# Power_Supply.net
KiCad netlist of a schematic drawn in Altium Designer
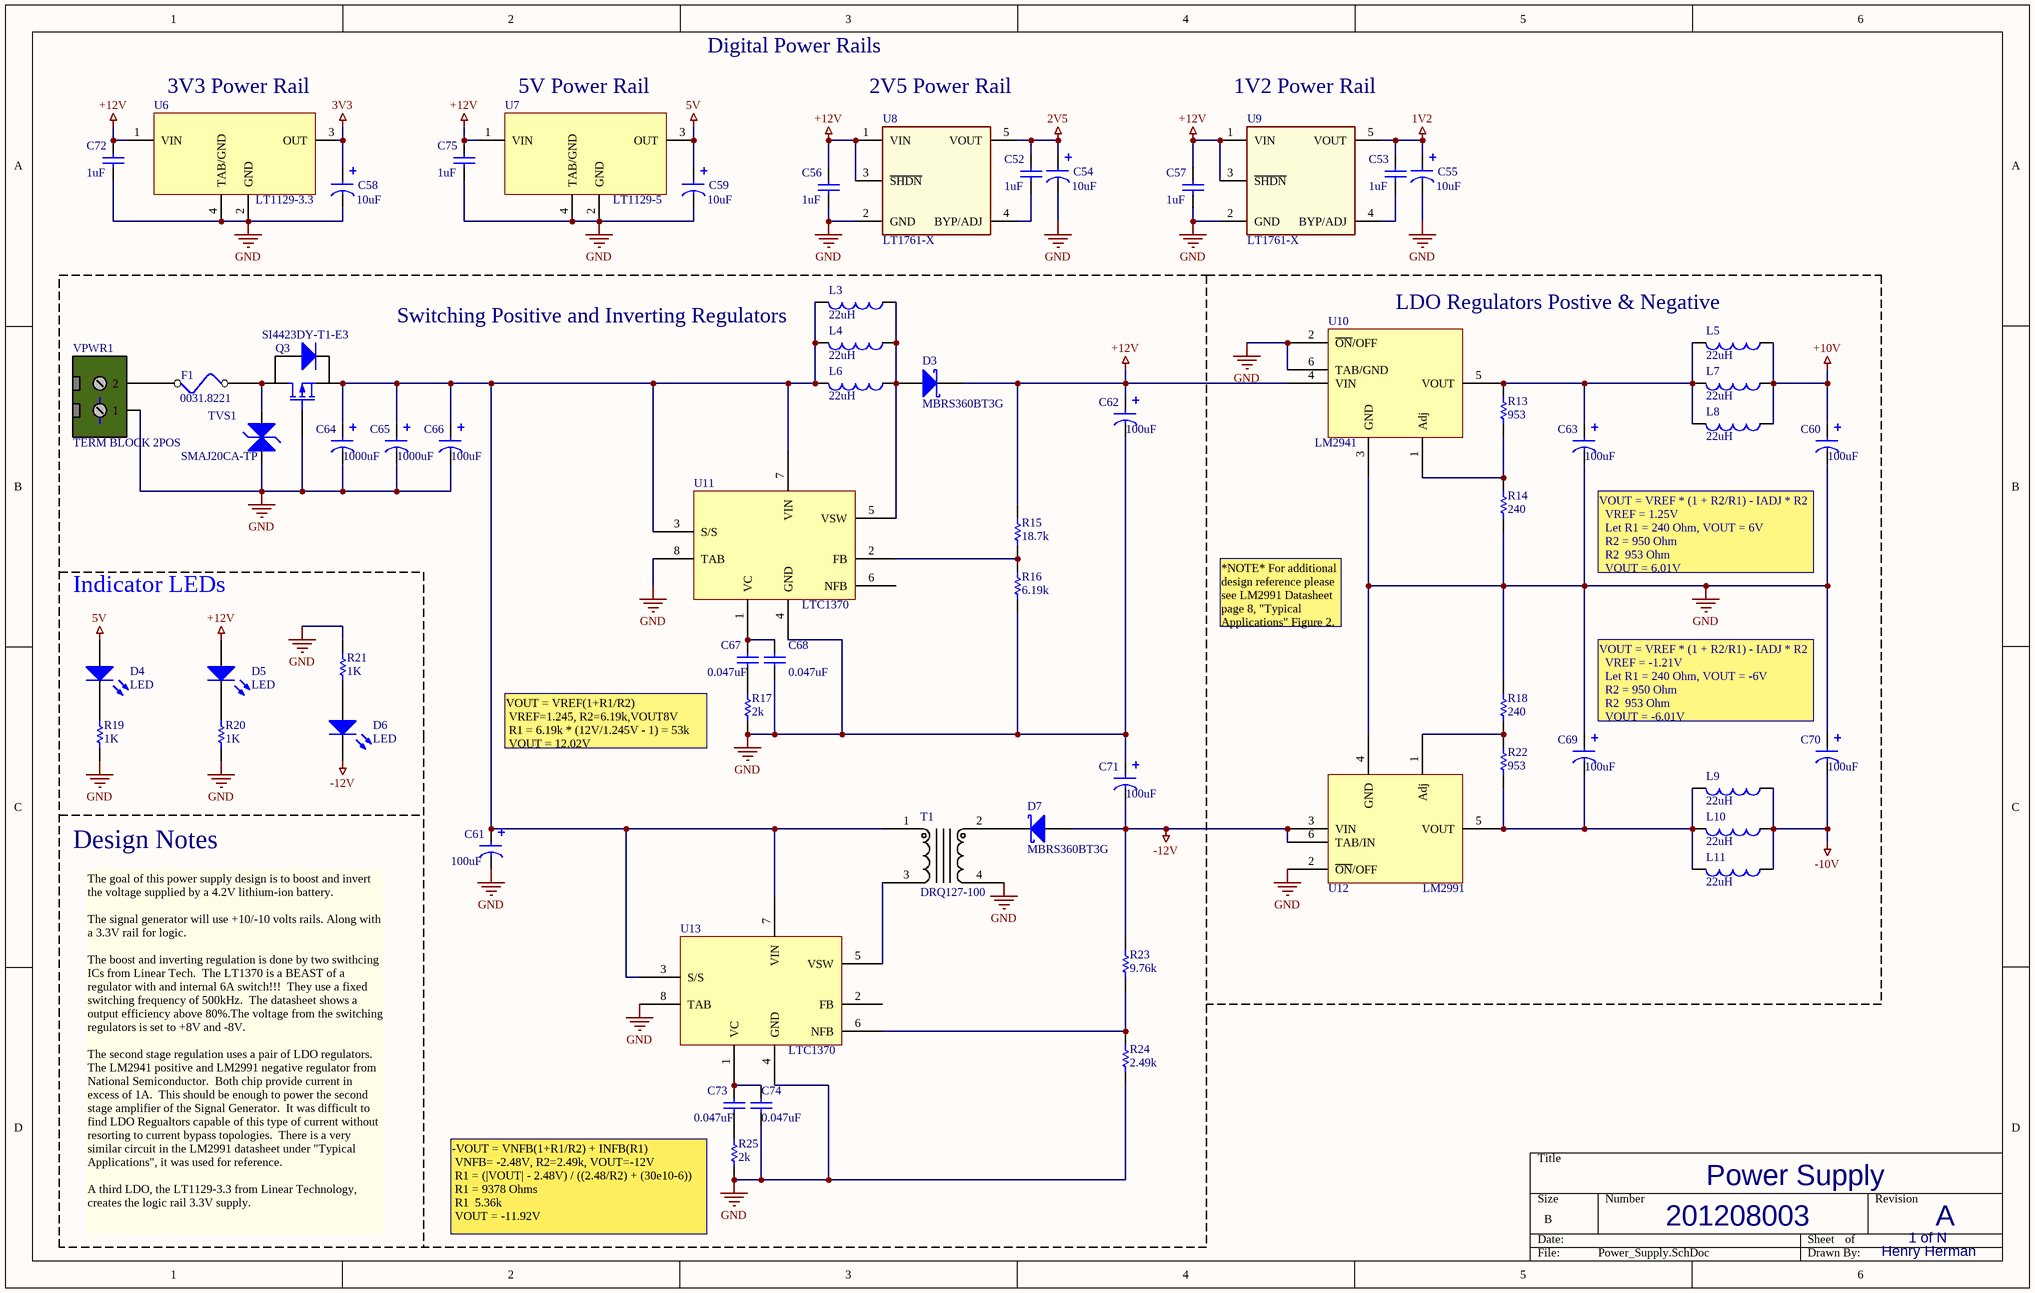
[diagram p0: Power_Supply.SchDoc]

(export (version "E")
  (design (tool "Eeschema 10.0.6"))
  (components
    (comp (ref "C52")
      (value "CAP")
      (footprint "SM/C_0603")
      (fields (field (name "LABEL") "1uF"))
      (libsource (lib "Henry1_20_2010") (part "CAP"))
    )
    (comp (ref "C53")
      (value "CAP")
      (footprint "SM/C_0603")
      (fields (field (name "LABEL") "1uF"))
      (libsource (lib "Henry1_20_2010") (part "CAP"))
    )
    (comp (ref "C54")
      (value "CAP_POL")
      (footprint "SM/C_POL_0805")
      (description "CAP")
      (fields (field (name "LABEL") "10uF"))
      (libsource (lib "Henry1_20_2010") (part "CAP_POL"))
    )
    (comp (ref "C55")
      (value "CAP_POL")
      (footprint "SM/C_POL_0805")
      (description "CAP")
      (fields (field (name "LABEL") "10uF"))
      (libsource (lib "Henry1_20_2010") (part "CAP_POL"))
    )
    (comp (ref "C56")
      (value "CAP")
      (footprint "SM/C_0603")
      (fields (field (name "LABEL") "1uF"))
      (libsource (lib "Henry1_20_2010") (part "CAP"))
    )
    (comp (ref "C57")
      (value "CAP")
      (footprint "SM/C_0603")
      (fields (field (name "LABEL") "1uF"))
      (libsource (lib "Henry1_20_2010") (part "CAP"))
    )
    (comp (ref "C58")
      (value "10uF")
      (footprint "SM/C_POL_0805")
      (description "CAP")
      (fields (field (name "Comment") "CAP_POL"))
      (libsource (lib "Henry1_20_2010") (part "CAP_POL"))
    )
    (comp (ref "C59")
      (value "CAP_POL")
      (footprint "SM/C_POL_0805")
      (description "CAP")
      (fields (field (name "ALTIUM_VALUE") "10uF"))
      (libsource (lib "Henry1_20_2010") (part "CAP_POL"))
    )
    (comp (ref "C60")
      (value "CAP_POL")
      (footprint "SM/CT_6032_12")
      (description "CAP")
      (fields (field (name "LABEL") "100uF"))
      (libsource (lib "Henry1_20_2010") (part "CAP_POL"))
    )
    (comp (ref "C61")
      (value "CAP_POL")
      (footprint "SM/CT_6032_12")
      (description "CAP")
      (fields (field (name "LABEL") "100uF"))
      (libsource (lib "Henry1_20_2010") (part "CAP_POL"))
    )
    (comp (ref "C62")
      (value "CAP_POL")
      (footprint "SM/CT_6032_12")
      (description "CAP")
      (fields (field (name "LABEL") "100uF"))
      (libsource (lib "Henry1_20_2010") (part "CAP_POL"))
    )
    (comp (ref "C63")
      (value "CAP_POL")
      (footprint "SM/CT_6032_12")
      (description "CAP")
      (fields (field (name "LABEL") "100uF"))
      (libsource (lib "Henry1_20_2010") (part "CAP_POL"))
    )
    (comp (ref "C64")
      (value "CAP_POL")
      (footprint "CAP-CAN-SMD-POL-12.5mmDia")
      (description "CAP")
      (fields (field (name "LABEL") "1000uF"))
      (libsource (lib "Henry1_20_2010") (part "CAP_POL"))
    )
    (comp (ref "C65")
      (value "CAP_POL")
      (footprint "CAP-CAN-SMD-POL-12.5mmDia")
      (description "CAP")
      (fields (field (name "LABEL") "1000uF"))
      (libsource (lib "Henry1_20_2010") (part "CAP_POL"))
    )
    (comp (ref "C66")
      (value "CAP_POL")
      (footprint "SM/CT_6032_12")
      (description "CAP")
      (fields (field (name "LABEL") "100uF"))
      (libsource (lib "Henry1_20_2010") (part "CAP_POL"))
    )
    (comp (ref "C67")
      (value "CAP")
      (footprint "SM/C_0603")
      (fields (field (name "LABEL") "0.047uF"))
      (libsource (lib "Henry1_20_2010") (part "CAP"))
    )
    (comp (ref "C68")
      (value "CAP")
      (footprint "SM/C_0603")
      (fields (field (name "LABEL") "0.047uF"))
      (libsource (lib "Henry1_20_2010") (part "CAP"))
    )
    (comp (ref "C69")
      (value "CAP_POL")
      (footprint "SM/CT_6032_12")
      (description "CAP")
      (fields (field (name "LABEL") "100uF"))
      (libsource (lib "Henry1_20_2010") (part "CAP_POL"))
    )
    (comp (ref "C70")
      (value "CAP_POL")
      (footprint "SM/CT_6032_12")
      (description "CAP")
      (fields (field (name "LABEL") "100uF"))
      (libsource (lib "Henry1_20_2010") (part "CAP_POL"))
    )
    (comp (ref "C71")
      (value "CAP_POL")
      (footprint "SM/CT_6032_12")
      (description "CAP")
      (fields (field (name "LABEL") "100uF"))
      (libsource (lib "Henry1_20_2010") (part "CAP_POL"))
    )
    (comp (ref "C72")
      (value "CAP")
      (footprint "SM/C_0603")
      (fields (field (name "LABEL") "1uF"))
      (libsource (lib "Henry1_20_2010") (part "CAP"))
    )
    (comp (ref "C73")
      (value "CAP")
      (footprint "SM/C_0603")
      (fields (field (name "LABEL") "0.047uF"))
      (libsource (lib "Henry1_20_2010") (part "CAP"))
    )
    (comp (ref "C74")
      (value "CAP")
      (footprint "SM/C_0603")
      (fields (field (name "LABEL") "0.047uF"))
      (libsource (lib "Henry1_20_2010") (part "CAP"))
    )
    (comp (ref "C75")
      (value "CAP")
      (footprint "SM/C_0603")
      (fields (field (name "LABEL") "1uF"))
      (libsource (lib "Henry1_20_2010") (part "CAP"))
    )
    (comp (ref "D3")
      (value "MBRS360BT3G")
      (footprint "DPAK-MBRD835L")
      (libsource (lib "Henry1_20_2010") (part "Schottky Diode"))
    )
    (comp (ref "D4") (value "LED") (footprint "LED-1206") (libsource (lib "Henry1_20_2010") (part "LED")))
    (comp (ref "D5") (value "LED") (footprint "LED-1206") (libsource (lib "Henry1_20_2010") (part "LED")))
    (comp (ref "D6") (value "LED") (footprint "LED-1206") (libsource (lib "Henry1_20_2010") (part "LED")))
    (comp (ref "D7")
      (value "MBRS360BT3G")
      (footprint "DPAK-MBRD835L")
      (libsource (lib "Henry1_20_2010") (part "Schottky Diode"))
    )
    (comp (ref "F1")
      (value "0031.8221")
      (footprint "SCHURTER/SMD/2 PADS/0031.8221")
      (description "FUSEHOLDER BLACK FOR SMD 5X20MM")
      (libsource (lib "FriedParts") (part "FUSE"))
    )
    (comp (ref "L3")
      (value "22uH")
      (footprint "G_JMETRIC/TDK/SLE10145")
      (description "INDUCTOR SHIELD PWR 22UH 10145")
      (fields (field (name "MFRPARTNUM") "SLF10145T-220M1R9-PF"))
      (libsource (lib "FriedParts") (part "INDUCTOR"))
    )
    (comp (ref "L4")
      (value "22uH")
      (footprint "G_JMETRIC/TDK/SLE10145")
      (description "INDUCTOR SHIELD PWR 22UH 10145")
      (fields (field (name "MFRPARTNUM") "SLF10145T-220M1R9-PF"))
      (libsource (lib "FriedParts") (part "INDUCTOR"))
    )
    (comp (ref "L5")
      (value "22uH")
      (footprint "G_JMETRIC/TDK/SLE10145")
      (description "INDUCTOR SHIELD PWR 22UH 10145")
      (fields (field (name "MFRPARTNUM") "SLF10145T-220M1R9-PF"))
      (libsource (lib "FriedParts") (part "INDUCTOR"))
    )
    (comp (ref "L6")
      (value "22uH")
      (footprint "G_JMETRIC/TDK/SLE10145")
      (description "INDUCTOR SHIELD PWR 22UH 10145")
      (fields (field (name "MFRPARTNUM") "SLF10145T-220M1R9-PF"))
      (libsource (lib "FriedParts") (part "INDUCTOR"))
    )
    (comp (ref "L7")
      (value "22uH")
      (footprint "G_JMETRIC/TDK/SLE10145")
      (description "INDUCTOR SHIELD PWR 22UH 10145")
      (fields (field (name "MFRPARTNUM") "SLF10145T-220M1R9-PF"))
      (libsource (lib "FriedParts") (part "INDUCTOR"))
    )
    (comp (ref "L8")
      (value "22uH")
      (footprint "G_JMETRIC/TDK/SLE10145")
      (description "INDUCTOR SHIELD PWR 22UH 10145")
      (fields (field (name "MFRPARTNUM") "SLF10145T-220M1R9-PF"))
      (libsource (lib "FriedParts") (part "INDUCTOR"))
    )
    (comp (ref "L9")
      (value "22uH")
      (footprint "G_JMETRIC/TDK/SLE10145")
      (description "INDUCTOR SHIELD PWR 22UH 10145")
      (fields (field (name "MFRPARTNUM") "SLF10145T-220M1R9-PF"))
      (libsource (lib "FriedParts") (part "INDUCTOR"))
    )
    (comp (ref "L10")
      (value "22uH")
      (footprint "G_JMETRIC/TDK/SLE10145")
      (description "INDUCTOR SHIELD PWR 22UH 10145")
      (fields (field (name "MFRPARTNUM") "SLF10145T-220M1R9-PF"))
      (libsource (lib "FriedParts") (part "INDUCTOR"))
    )
    (comp (ref "L11")
      (value "22uH")
      (footprint "G_JMETRIC/TDK/SLE10145")
      (description "INDUCTOR SHIELD PWR 22UH 10145")
      (fields (field (name "MFRPARTNUM") "SLF10145T-220M1R9-PF"))
      (libsource (lib "FriedParts") (part "INDUCTOR"))
    )
    (comp (ref "Q3")
      (value "SI4423DY-T1-E3")
      (footprint "SOIC-8-Lead-Vishay-PFET")
      (description "mosfet,p ch,20v,10a,8soic; transistor polarity:p channel;")
      (libsource (lib "FriedParts") (part "P-Channel 20V D-S MOSFET"))
    )
    (comp (ref "R13")
      (value "953")
      (footprint "SM/R_0603")
      (description "Resistor")
      (fields (field (name "Comment") "Res") (field (name "PUBLISHER") "Altium Limited"))
      (libsource (lib "Henry1_20_2010") (part "Res"))
    )
    (comp (ref "R14")
      (value "240")
      (footprint "SM/R_0603")
      (description "Resistor")
      (fields (field (name "Comment") "Res") (field (name "PUBLISHER") "Altium Limited"))
      (libsource (lib "Henry1_20_2010") (part "Res"))
    )
    (comp (ref "R15")
      (value "18.7k")
      (footprint "SM/R_0603")
      (description "Resistor")
      (fields (field (name "Comment") "Res") (field (name "PUBLISHER") "Altium Limited"))
      (libsource (lib "Henry1_20_2010") (part "Res"))
    )
    (comp (ref "R16")
      (value "6.19k")
      (footprint "SM/R_0603")
      (description "Resistor")
      (fields (field (name "Comment") "Res") (field (name "PUBLISHER") "Altium Limited"))
      (libsource (lib "Henry1_20_2010") (part "Res"))
    )
    (comp (ref "R17")
      (value "2k")
      (footprint "SM/R_0603")
      (description "Resistor")
      (fields (field (name "Comment") "Res") (field (name "PUBLISHER") "Altium Limited"))
      (libsource (lib "Henry1_20_2010") (part "Res"))
    )
    (comp (ref "R18")
      (value "240")
      (footprint "SM/R_0603")
      (description "Resistor")
      (fields (field (name "Comment") "Res") (field (name "PUBLISHER") "Altium Limited"))
      (libsource (lib "Henry1_20_2010") (part "Res"))
    )
    (comp (ref "R19")
      (value "1K")
      (footprint "SM/R_0603")
      (description "Resistor")
      (fields (field (name "Comment") "Res") (field (name "PUBLISHER") "Altium Limited"))
      (libsource (lib "Henry1_20_2010") (part "Res"))
    )
    (comp (ref "R20")
      (value "1K")
      (footprint "SM/R_0603")
      (description "Resistor")
      (fields (field (name "Comment") "Res") (field (name "PUBLISHER") "Altium Limited"))
      (libsource (lib "Henry1_20_2010") (part "Res"))
    )
    (comp (ref "R21")
      (value "1K")
      (footprint "SM/R_0603")
      (description "Resistor")
      (fields (field (name "Comment") "Res") (field (name "PUBLISHER") "Altium Limited"))
      (libsource (lib "Henry1_20_2010") (part "Res"))
    )
    (comp (ref "R22")
      (value "953")
      (footprint "SM/R_0603")
      (description "Resistor")
      (fields (field (name "Comment") "Res") (field (name "PUBLISHER") "Altium Limited"))
      (libsource (lib "Henry1_20_2010") (part "Res"))
    )
    (comp (ref "R23")
      (value "9.76k")
      (footprint "SM/R_0603")
      (description "Resistor")
      (fields (field (name "Comment") "Res") (field (name "PUBLISHER") "Altium Limited"))
      (libsource (lib "Henry1_20_2010") (part "Res"))
    )
    (comp (ref "R24")
      (value "2.49k")
      (footprint "SM/R_0603")
      (description "Resistor")
      (fields (field (name "Comment") "Res") (field (name "PUBLISHER") "Altium Limited"))
      (libsource (lib "Henry1_20_2010") (part "Res"))
    )
    (comp (ref "R25")
      (value "2k")
      (footprint "SM/R_0603")
      (description "Resistor")
      (fields (field (name "Comment") "Res") (field (name "PUBLISHER") "Altium Limited"))
      (libsource (lib "Henry1_20_2010") (part "Res"))
    )
    (comp (ref "T1")
      (value "DRQ127-100")
      (footprint "DRQ127-100")
      (libsource (lib "Henry1_20_2010") (part "DRQ127-100-XFORM-1{colon}1"))
    )
    (comp (ref "TVS1")
      (value "SMAJ20CA-TP")
      (footprint "D0-214AC")
      (description "TVS 400W 12V BIDIRECT SMA")
      (fields (field (name "MFRPARTNUM") "SMAJ12CA-TP"))
      (libsource (lib "FriedParts") (part "SMAJ12CA-TPMC"))
    )
    (comp (ref "U6")
      (value "LT1129-3.3")
      (footprint "SOT223-3Lead-STPackage-LinearTechLT1129-3.3")
      (libsource (lib "Henry1_20_2010") (part "LT1129-3.3"))
    )
    (comp (ref "U7")
      (value "LT1129-5")
      (footprint "SOT223-3Lead-STPackage-LinearTechLT1129-3.3")
      (libsource (lib "Henry1_20_2010") (part "LT1129-5"))
    )
    (comp (ref "U8")
      (value "LT1761-X")
      (footprint "TSOT-23-5Lead-LTC3406A")
      (libsource (lib "Henry1_20_2010") (part "LT1761-X"))
    )
    (comp (ref "U9")
      (value "LT1761-X")
      (footprint "TSOT-23-5Lead-LTC3406A")
      (libsource (lib "Henry1_20_2010") (part "LT1761-X"))
    )
    (comp (ref "U10")
      (value "LM2941")
      (footprint "T0-263- 5Lead - National Semi - LM2941")
      (libsource (lib "Henry1_20_2010") (part "LM2941-LDO Regulator"))
    )
    (comp (ref "U11")
      (value "LTC1370")
      (footprint "DDPak-7Lead-RPackage-linear")
      (libsource (lib "Henry1_20_2010") (part "LT1370"))
    )
    (comp (ref "U12")
      (value "LM2991")
      (footprint "T0-263 5Lead SMP - National Semi - LM2991S")
      (libsource (lib "Henry1_20_2010") (part "LM2991-Negative LDO Regulator"))
    )
    (comp (ref "U13")
      (value "LTC1370")
      (footprint "DDPak-7Lead-RPackage-linear")
      (libsource (lib "Henry1_20_2010") (part "LT1370"))
    )
    (comp (ref "VPWR1")
      (value "TERM BLOCK 2POS")
      (footprint "Conn-ScrewTerminal-2pin-Phoenix")
      (libsource (lib "Henry1_20_2010") (part "2Pin-PhoenixTerminalBlock"))
    )
  )
  (nets
    (net (code "1") (name "+10V") (class "Default")
      (node (ref "C60") (pin "1") (pinfunction "1_1") (pintype "passive"))
      (node (ref "L5") (pin "1") (pinfunction "1_1") (pintype "passive"))
      (node (ref "L7") (pin "1") (pinfunction "1_1") (pintype "passive"))
      (node (ref "L8") (pin "1") (pinfunction "1_1") (pintype "passive"))
    )
    (net (code "2") (name "+12V") (class "Default")
      (node (ref "C56") (pin "2") (pinfunction "2_2") (pintype "passive"))
      (node (ref "C57") (pin "2") (pinfunction "2_2") (pintype "passive"))
      (node (ref "C62") (pin "1") (pinfunction "1_1") (pintype "passive"))
      (node (ref "C72") (pin "2") (pinfunction "2_2") (pintype "passive"))
      (node (ref "C75") (pin "2") (pinfunction "2_2") (pintype "passive"))
      (node (ref "D3") (pin "K") (pinfunction "K_K") (pintype "passive"))
      (node (ref "D5") (pin "1") (pinfunction "A_1") (pintype "passive"))
      (node (ref "R15") (pin "2") (pinfunction "2_2") (pintype "passive"))
      (node (ref "U10") (pin "4") (pinfunction "VIN_4") (pintype "passive"))
      (node (ref "U6") (pin "1") (pinfunction "VIN_1") (pintype "passive"))
      (node (ref "U7") (pin "1") (pinfunction "VIN_1") (pintype "passive"))
      (node (ref "U8") (pin "1") (pinfunction "VIN_1") (pintype "power_in"))
      (node (ref "U8") (pin "3") (pinfunction "~{SHDN}_3") (pintype "power_in"))
      (node (ref "U9") (pin "1") (pinfunction "VIN_1") (pintype "power_in"))
      (node (ref "U9") (pin "3") (pinfunction "~{SHDN}_3") (pintype "power_in"))
    )
    (net (code "3") (name "-10V") (class "Default")
      (node (ref "C70") (pin "2") (pinfunction "2_2") (pintype "passive"))
      (node (ref "L10") (pin "1") (pinfunction "1_1") (pintype "passive"))
      (node (ref "L11") (pin "1") (pinfunction "1_1") (pintype "passive"))
      (node (ref "L9") (pin "1") (pinfunction "1_1") (pintype "passive"))
    )
    (net (code "4") (name "-12V") (class "Default")
      (node (ref "C71") (pin "2") (pinfunction "2_2") (pintype "passive"))
      (node (ref "D6") (pin "2") (pinfunction "K_2") (pintype "passive"))
      (node (ref "D7") (pin "A") (pinfunction "A_A") (pintype "passive"))
      (node (ref "R23") (pin "2") (pinfunction "2_2") (pintype "passive"))
      (node (ref "U12") (pin "3") (pinfunction "VIN_3") (pintype "passive"))
      (node (ref "U12") (pin "6") (pinfunction "TAB/IN_6") (pintype "passive"))
    )
    (net (code "5") (name "1V2") (class "Default")
      (node (ref "C53") (pin "2") (pinfunction "2_2") (pintype "passive"))
      (node (ref "C55") (pin "1") (pinfunction "1_1") (pintype "passive"))
      (node (ref "U9") (pin "5") (pinfunction "VOUT_5") (pintype "power_in"))
    )
    (net (code "6") (name "2V5") (class "Default")
      (node (ref "C52") (pin "2") (pinfunction "2_2") (pintype "passive"))
      (node (ref "C54") (pin "1") (pinfunction "1_1") (pintype "passive"))
      (node (ref "U8") (pin "5") (pinfunction "VOUT_5") (pintype "power_in"))
    )
    (net (code "7") (name "3V3") (class "Default")
      (node (ref "C58") (pin "1") (pinfunction "1_1") (pintype "passive"))
      (node (ref "U6") (pin "3") (pinfunction "OUT_3") (pintype "passive"))
    )
    (net (code "8") (name "5V") (class "Default")
      (node (ref "C59") (pin "1") (pinfunction "1_1") (pintype "passive"))
      (node (ref "D4") (pin "1") (pinfunction "A_1") (pintype "passive"))
      (node (ref "U7") (pin "3") (pinfunction "OUT_3") (pintype "passive"))
    )
    (net (code "9") (name "GND") (class "Default")
      (node (ref "C54") (pin "2") (pinfunction "2_2") (pintype "passive"))
      (node (ref "C55") (pin "2") (pinfunction "2_2") (pintype "passive"))
      (node (ref "C56") (pin "1") (pinfunction "1_1") (pintype "passive"))
      (node (ref "C57") (pin "1") (pinfunction "1_1") (pintype "passive"))
      (node (ref "C58") (pin "2") (pinfunction "2_2") (pintype "passive"))
      (node (ref "C59") (pin "2") (pinfunction "2_2") (pintype "passive"))
      (node (ref "C60") (pin "2") (pinfunction "2_2") (pintype "passive"))
      (node (ref "C61") (pin "2") (pinfunction "2_2") (pintype "passive"))
      (node (ref "C62") (pin "2") (pinfunction "2_2") (pintype "passive"))
      (node (ref "C63") (pin "2") (pinfunction "2_2") (pintype "passive"))
      (node (ref "C64") (pin "2") (pinfunction "2_2") (pintype "passive"))
      (node (ref "C65") (pin "2") (pinfunction "2_2") (pintype "passive"))
      (node (ref "C66") (pin "2") (pinfunction "2_2") (pintype "passive"))
      (node (ref "C68") (pin "1") (pinfunction "1_1") (pintype "passive"))
      (node (ref "C69") (pin "1") (pinfunction "1_1") (pintype "passive"))
      (node (ref "C70") (pin "1") (pinfunction "1_1") (pintype "passive"))
      (node (ref "C71") (pin "1") (pinfunction "1_1") (pintype "passive"))
      (node (ref "C72") (pin "1") (pinfunction "1_1") (pintype "passive"))
      (node (ref "C74") (pin "1") (pinfunction "1_1") (pintype "passive"))
      (node (ref "C75") (pin "1") (pinfunction "1_1") (pintype "passive"))
      (node (ref "Q3") (pin "G") (pinfunction "G_G") (pintype "passive"))
      (node (ref "R14") (pin "1") (pinfunction "1_1") (pintype "passive"))
      (node (ref "R16") (pin "1") (pinfunction "1_1") (pintype "passive"))
      (node (ref "R17") (pin "1") (pinfunction "1_1") (pintype "passive"))
      (node (ref "R18") (pin "2") (pinfunction "2_2") (pintype "passive"))
      (node (ref "R19") (pin "1") (pinfunction "1_1") (pintype "passive"))
      (node (ref "R20") (pin "1") (pinfunction "1_1") (pintype "passive"))
      (node (ref "R21") (pin "2") (pinfunction "2_2") (pintype "passive"))
      (node (ref "R24") (pin "1") (pinfunction "1_1") (pintype "passive"))
      (node (ref "R25") (pin "1") (pinfunction "1_1") (pintype "passive"))
      (node (ref "T1") (pin "4") (pinfunction "4_4") (pintype "passive"))
      (node (ref "TVS1") (pin "C") (pinfunction "1_C") (pintype "passive"))
      (node (ref "U10") (pin "2") (pinfunction "~{ON}/OFF_2") (pintype "passive"))
      (node (ref "U10") (pin "3") (pinfunction "GND_3") (pintype "passive"))
      (node (ref "U10") (pin "6") (pinfunction "TAB/GND_6") (pintype "passive"))
      (node (ref "U11") (pin "4") (pinfunction "GND_4") (pintype "passive"))
      (node (ref "U11") (pin "8") (pinfunction "TAB_8") (pintype "passive"))
      (node (ref "U12") (pin "2") (pinfunction "~{ON}/OFF_2") (pintype "passive"))
      (node (ref "U12") (pin "4") (pinfunction "GND_4") (pintype "passive"))
      (node (ref "U13") (pin "4") (pinfunction "GND_4") (pintype "passive"))
      (node (ref "U13") (pin "8") (pinfunction "TAB_8") (pintype "passive"))
      (node (ref "U6") (pin "2") (pinfunction "GND_2") (pintype "passive"))
      (node (ref "U6") (pin "4") (pinfunction "TAB/GND_4") (pintype "passive"))
      (node (ref "U7") (pin "2") (pinfunction "GND_2") (pintype "passive"))
      (node (ref "U7") (pin "4") (pinfunction "TAB/GND_4") (pintype "passive"))
      (node (ref "U8") (pin "2") (pinfunction "GND_2") (pintype "power_in"))
      (node (ref "U9") (pin "2") (pinfunction "GND_2") (pintype "power_in"))
      (node (ref "VPWR1") (pin "1") (pinfunction "1_1") (pintype "passive"))
    )
    (net (code "10") (name "Net-(C67-Pad1)") (class "Default")
      (node (ref "C67") (pin "1") (pinfunction "1_1") (pintype "passive"))
      (node (ref "R17") (pin "2") (pinfunction "2_2") (pintype "passive"))
    )
    (net (code "11") (name "Net-(C73-Pad1)") (class "Default")
      (node (ref "C73") (pin "1") (pinfunction "1_1") (pintype "passive"))
      (node (ref "R25") (pin "2") (pinfunction "2_2") (pintype "passive"))
    )
    (net (code "12") (name "Net-(D4-K)") (class "Default")
      (node (ref "D4") (pin "2") (pinfunction "K_2") (pintype "passive"))
      (node (ref "R19") (pin "2") (pinfunction "2_2") (pintype "passive"))
    )
    (net (code "13") (name "Net-(D5-K)") (class "Default")
      (node (ref "D5") (pin "2") (pinfunction "K_2") (pintype "passive"))
      (node (ref "R20") (pin "2") (pinfunction "2_2") (pintype "passive"))
    )
    (net (code "14") (name "Net-(D6-A)") (class "Default")
      (node (ref "D6") (pin "1") (pinfunction "A_1") (pintype "passive"))
      (node (ref "R21") (pin "1") (pinfunction "1_1") (pintype "passive"))
    )
    (net (code "15") (name "Net-(D7-PadK)") (class "Default")
      (node (ref "D7") (pin "K") (pinfunction "K_K") (pintype "passive"))
      (node (ref "T1") (pin "2") (pinfunction "2_2") (pintype "passive"))
    )
    (net (code "16") (name "Net-(F1-Pad1)") (class "Default")
      (node (ref "F1") (pin "1") (pinfunction "1_1") (pintype "passive"))
      (node (ref "VPWR1") (pin "2") (pinfunction "2_2") (pintype "passive"))
    )
    (net (code "17") (name "Net-(T1-P1)") (class "Default")
      (node (ref "C61") (pin "1") (pinfunction "1_1") (pintype "passive"))
      (node (ref "C64") (pin "1") (pinfunction "1_1") (pintype "passive"))
      (node (ref "C65") (pin "1") (pinfunction "1_1") (pintype "passive"))
      (node (ref "C66") (pin "1") (pinfunction "1_1") (pintype "passive"))
      (node (ref "L3") (pin "2") (pinfunction "2_2") (pintype "passive"))
      (node (ref "L4") (pin "2") (pinfunction "2_2") (pintype "passive"))
      (node (ref "L6") (pin "2") (pinfunction "2_2") (pintype "passive"))
      (node (ref "Q3") (pin "S") (pinfunction "S_S") (pintype "passive"))
      (node (ref "T1") (pin "1") (pinfunction "P1_1") (pintype "passive"))
      (node (ref "U11") (pin "3") (pinfunction "S/S_3") (pintype "passive"))
      (node (ref "U11") (pin "7") (pinfunction "VIN_7") (pintype "passive"))
      (node (ref "U13") (pin "3") (pinfunction "S/S_3") (pintype "passive"))
      (node (ref "U13") (pin "7") (pinfunction "VIN_7") (pintype "passive"))
    )
    (net (code "18") (name "Net-(TVS1-2)") (class "Default")
      (node (ref "F1") (pin "2") (pinfunction "2_2") (pintype "passive"))
      (node (ref "Q3") (pin "D") (pinfunction "D_D") (pintype "passive"))
      (node (ref "TVS1") (pin "A") (pinfunction "2_A") (pintype "passive"))
    )
    (net (code "19") (name "Net-(U8-BYP{slash}ADJ)") (class "Default")
      (node (ref "C52") (pin "1") (pinfunction "1_1") (pintype "passive"))
      (node (ref "U8") (pin "4") (pinfunction "BYP/ADJ_4") (pintype "power_in"))
    )
    (net (code "20") (name "Net-(U9-BYP{slash}ADJ)") (class "Default")
      (node (ref "C53") (pin "1") (pinfunction "1_1") (pintype "passive"))
      (node (ref "U9") (pin "4") (pinfunction "BYP/ADJ_4") (pintype "power_in"))
    )
    (net (code "21") (name "Net-(U10-Adj)") (class "Default")
      (node (ref "R13") (pin "1") (pinfunction "1_1") (pintype "passive"))
      (node (ref "R14") (pin "2") (pinfunction "2_2") (pintype "passive"))
      (node (ref "U10") (pin "1") (pinfunction "Adj_1") (pintype "passive"))
    )
    (net (code "22") (name "Net-(U10-VOUT)") (class "Default")
      (node (ref "C63") (pin "1") (pinfunction "1_1") (pintype "passive"))
      (node (ref "L5") (pin "2") (pinfunction "2_2") (pintype "passive"))
      (node (ref "L7") (pin "2") (pinfunction "2_2") (pintype "passive"))
      (node (ref "L8") (pin "2") (pinfunction "2_2") (pintype "passive"))
      (node (ref "R13") (pin "2") (pinfunction "2_2") (pintype "passive"))
      (node (ref "U10") (pin "5") (pinfunction "VOUT_5") (pintype "passive"))
    )
    (net (code "23") (name "Net-(U11-FB)") (class "Default")
      (node (ref "R15") (pin "1") (pinfunction "1_1") (pintype "passive"))
      (node (ref "R16") (pin "2") (pinfunction "2_2") (pintype "passive"))
      (node (ref "U11") (pin "2") (pinfunction "FB_2") (pintype "passive"))
    )
    (net (code "24") (name "Net-(U11-VC)") (class "Default")
      (node (ref "C67") (pin "2") (pinfunction "2_2") (pintype "passive"))
      (node (ref "C68") (pin "2") (pinfunction "2_2") (pintype "passive"))
      (node (ref "U11") (pin "1") (pinfunction "VC_1") (pintype "passive"))
    )
    (net (code "25") (name "Net-(U11-VSW)") (class "Default")
      (node (ref "D3") (pin "A") (pinfunction "A_A") (pintype "passive"))
      (node (ref "L3") (pin "1") (pinfunction "1_1") (pintype "passive"))
      (node (ref "L4") (pin "1") (pinfunction "1_1") (pintype "passive"))
      (node (ref "L6") (pin "1") (pinfunction "1_1") (pintype "passive"))
      (node (ref "U11") (pin "5") (pinfunction "VSW_5") (pintype "passive"))
    )
    (net (code "26") (name "Net-(U12-Adj)") (class "Default")
      (node (ref "R18") (pin "1") (pinfunction "1_1") (pintype "passive"))
      (node (ref "R22") (pin "2") (pinfunction "2_2") (pintype "passive"))
      (node (ref "U12") (pin "1") (pinfunction "Adj_1") (pintype "passive"))
    )
    (net (code "27") (name "Net-(U12-VOUT)") (class "Default")
      (node (ref "C69") (pin "2") (pinfunction "2_2") (pintype "passive"))
      (node (ref "L10") (pin "2") (pinfunction "2_2") (pintype "passive"))
      (node (ref "L11") (pin "2") (pinfunction "2_2") (pintype "passive"))
      (node (ref "L9") (pin "2") (pinfunction "2_2") (pintype "passive"))
      (node (ref "R22") (pin "1") (pinfunction "1_1") (pintype "passive"))
      (node (ref "U12") (pin "5") (pinfunction "VOUT_5") (pintype "passive"))
    )
    (net (code "28") (name "Net-(U13-NFB)") (class "Default")
      (node (ref "R23") (pin "1") (pinfunction "1_1") (pintype "passive"))
      (node (ref "R24") (pin "2") (pinfunction "2_2") (pintype "passive"))
      (node (ref "U13") (pin "6") (pinfunction "NFB_6") (pintype "passive"))
    )
    (net (code "29") (name "Net-(U13-VC)") (class "Default")
      (node (ref "C73") (pin "2") (pinfunction "2_2") (pintype "passive"))
      (node (ref "C74") (pin "2") (pinfunction "2_2") (pintype "passive"))
      (node (ref "U13") (pin "1") (pinfunction "VC_1") (pintype "passive"))
    )
    (net (code "30") (name "Net-(U13-VSW)") (class "Default")
      (node (ref "T1") (pin "3") (pinfunction "3_3") (pintype "passive"))
      (node (ref "U13") (pin "5") (pinfunction "VSW_5") (pintype "passive"))
    )
    (net (code "31") (name "unconnected-(U11-NFB-Pad6)") (class "Default")
      (node (ref "U11") (pin "6") (pinfunction "NFB_6") (pintype "passive"))
    )
    (net (code "32") (name "unconnected-(U13-FB-Pad2)") (class "Default")
      (node (ref "U13") (pin "2") (pinfunction "FB_2") (pintype "passive"))
    )
  )
)
